# pi_zero_shield_v1_KW.net
KiCad netlist of a schematic drawn in EAGLE
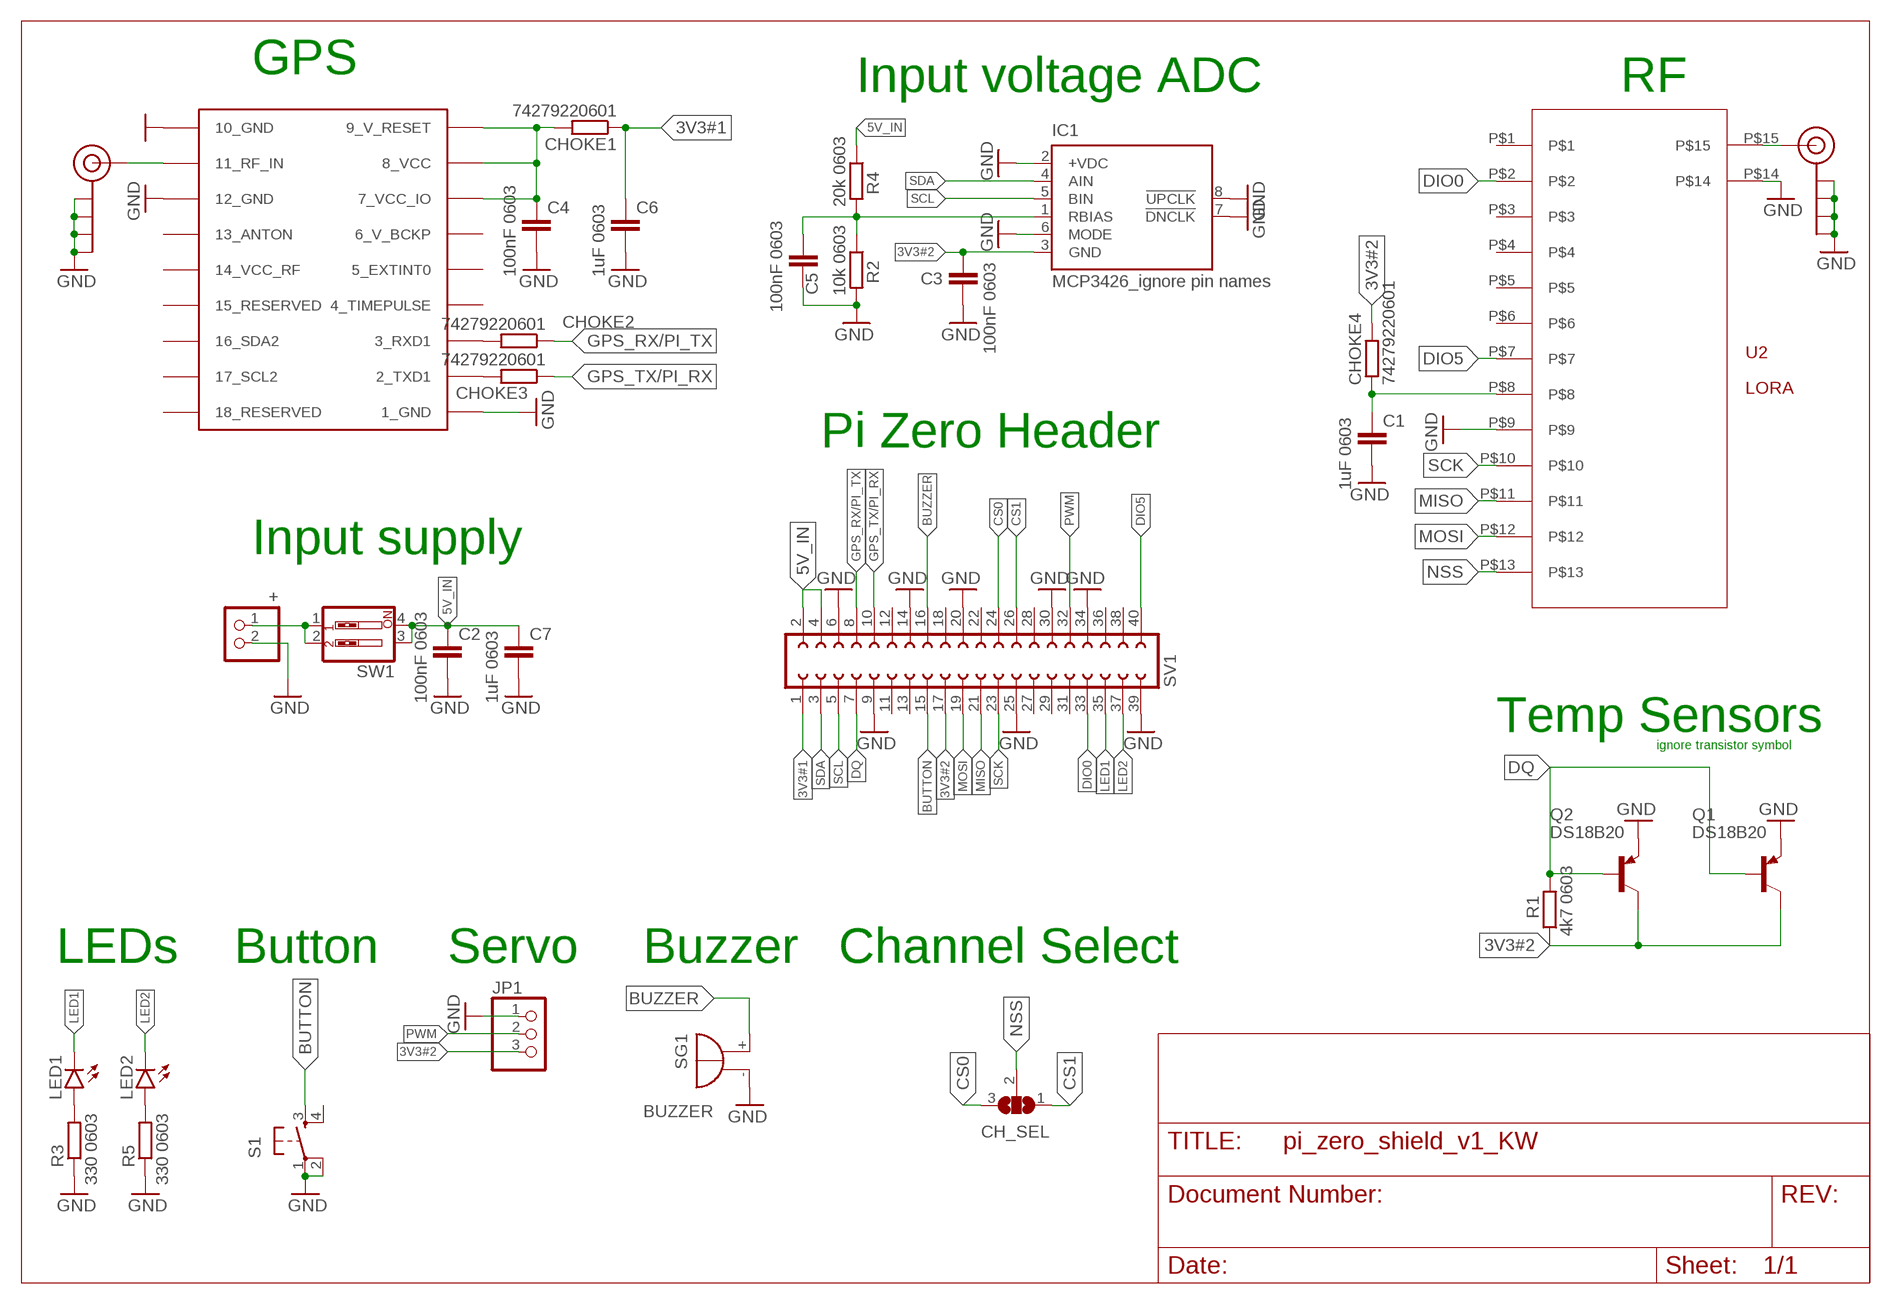
[diagram p0: schematic, sheet 1]

(export (version "E")
  (design (tool "Eeschema 10.0.6"))
  (components
    (comp (ref "+")
      (value "PINHD-1X2")
      (footprint "eagle-import:1X02")
      (libsource (lib "eagle-import") (part "PINHD-1X2"))
    )
    (comp (ref "C1")
      (value "1uF 0603")
      (footprint "eagle-import:C0603K")
      (libsource (lib "eagle-import") (part "C-EUC0603K"))
    )
    (comp (ref "C2")
      (value "100nF 0603")
      (footprint "eagle-import:C0603K")
      (libsource (lib "eagle-import") (part "C-EUC0603K"))
    )
    (comp (ref "C3")
      (value "100nF 0603")
      (footprint "eagle-import:C0603K")
      (libsource (lib "eagle-import") (part "C-EUC0603K"))
    )
    (comp (ref "C4")
      (value "100nF 0603")
      (footprint "eagle-import:C0603K")
      (libsource (lib "eagle-import") (part "C-EUC0603K"))
    )
    (comp (ref "C5")
      (value "100nF 0603")
      (footprint "eagle-import:C0603K")
      (libsource (lib "eagle-import") (part "C-EUC0603K"))
    )
    (comp (ref "C6")
      (value "1uF 0603")
      (footprint "eagle-import:C0603K")
      (libsource (lib "eagle-import") (part "C-EUC0603K"))
    )
    (comp (ref "C7")
      (value "1uF 0603")
      (footprint "eagle-import:C0603K")
      (libsource (lib "eagle-import") (part "C-EUC0603K"))
    )
    (comp (ref "CHOKE1")
      (value "74279220601")
      (footprint "eagle-import:M0805")
      (libsource (lib "eagle-import") (part "R-EU_M0805"))
    )
    (comp (ref "CHOKE2")
      (value "74279220601")
      (footprint "eagle-import:M0805")
      (libsource (lib "eagle-import") (part "R-EU_M0805"))
    )
    (comp (ref "CHOKE3")
      (value "74279220601")
      (footprint "eagle-import:M0805")
      (libsource (lib "eagle-import") (part "R-EU_M0805"))
    )
    (comp (ref "CHOKE4")
      (value "74279220601")
      (footprint "eagle-import:M0805")
      (libsource (lib "eagle-import") (part "R-EU_M0805"))
    )
    (comp (ref "CH_SEL")
      (value "SJ2W")
      (footprint "eagle-import:SJ_2")
      (libsource (lib "eagle-import") (part "SJ2W"))
    )
    (comp (ref "IC1")
      (value "MCP3426_ignore pin names")
      (footprint "eagle-import:SOIC08")
      (libsource (lib "eagle-import") (part "LS7183-SOIC"))
    )
    (comp (ref "J$1")
      (value "SMA_EDGE")
      (footprint "eagle-import:SMA-EDGE")
      (libsource (lib "eagle-import") (part "SMA_EDGE"))
    )
    (comp (ref "J$2")
      (value "SMA_EDGE")
      (footprint "eagle-import:SMA-EDGE")
      (libsource (lib "eagle-import") (part "SMA_EDGE"))
    )
    (comp (ref "JP1")
      (value "PINHD-1X3")
      (footprint "eagle-import:1X03")
      (libsource (lib "eagle-import") (part "PINHD-1X3"))
    )
    (comp (ref "LED1")
      (value "LEDSML0603")
      (footprint "eagle-import:SML0603")
      (libsource (lib "eagle-import") (part "LEDSML0603"))
    )
    (comp (ref "LED2")
      (value "LEDSML0603")
      (footprint "eagle-import:SML0603")
      (libsource (lib "eagle-import") (part "LEDSML0603"))
    )
    (comp (ref "Q1")
      (value "DS18B20")
      (footprint "eagle-import:TO92-CBE")
      (libsource (lib "eagle-import") (part "-?TO92MPSA56"))
    )
    (comp (ref "Q2")
      (value "DS18B20")
      (footprint "eagle-import:TO92-CBE")
      (libsource (lib "eagle-import") (part "-?TO92MPSA56"))
    )
    (comp (ref "R1")
      (value "4k7 0603")
      (footprint "eagle-import:R0603")
      (libsource (lib "eagle-import") (part "R-EU_R0603"))
    )
    (comp (ref "R2")
      (value "10k 0603")
      (footprint "eagle-import:R0603")
      (libsource (lib "eagle-import") (part "R-EU_R0603"))
    )
    (comp (ref "R3")
      (value "330 0603")
      (footprint "eagle-import:R0603")
      (libsource (lib "eagle-import") (part "R-EU_R0603"))
    )
    (comp (ref "R4")
      (value "20k 0603")
      (footprint "eagle-import:R0603")
      (libsource (lib "eagle-import") (part "R-EU_R0603"))
    )
    (comp (ref "R5")
      (value "330 0603")
      (footprint "eagle-import:R0603")
      (libsource (lib "eagle-import") (part "R-EU_R0603"))
    )
    (comp (ref "S1")
      (value "DTS-6")
      (footprint "eagle-import:DTS-6")
      (libsource (lib "eagle-import") (part "DTS-6"))
    )
    (comp (ref "SG1")
      (value "BUZZER")
      (footprint "eagle-import:BMT1205XH7.5")
      (libsource (lib "eagle-import") (part "BMT1205XH7.5"))
    )
    (comp (ref "SV1")
      (value "FE20-2")
      (footprint "eagle-import:FE20-2")
      (libsource (lib "eagle-import") (part "FE20-2"))
    )
    (comp (ref "SW1")
      (value "SW_DIP-2")
      (footprint "eagle-import:EDG-02")
      (libsource (lib "eagle-import") (part "SW_DIP-2"))
    )
    (comp (ref "U1")
      (value "U1")
      (footprint "eagle-import:UBLOX_MAX-6")
      (libsource (lib "eagle-import") (part "UBLOX_MAX-6"))
    )
    (comp (ref "U2")
      (value "LORA")
      (footprint "eagle-import:LORA_DRF")
      (libsource (lib "eagle-import") (part "LORA"))
    )
  )
  (nets
    (net (code "1") (name "3V3#1") (class "Default")
      (node (ref "C6") (pin "1") (pinfunction "1_1") (pintype "passive"))
      (node (ref "CHOKE1") (pin "1") (pinfunction "1_1") (pintype "passive"))
      (node (ref "SV1") (pin "1") (pinfunction "1_1") (pintype "passive"))
    )
    (net (code "2") (name "3V3#2") (class "Default")
      (node (ref "C3") (pin "1") (pinfunction "1_1") (pintype "passive"))
      (node (ref "CHOKE4") (pin "2") (pinfunction "2_2") (pintype "passive"))
      (node (ref "IC1") (pin "3") (pinfunction "GND_3") (pintype "power_in"))
      (node (ref "JP1") (pin "3") (pinfunction "3_3") (pintype "passive"))
      (node (ref "Q1") (pin "C") (pinfunction "C_C") (pintype "passive"))
      (node (ref "Q2") (pin "C") (pinfunction "C_C") (pintype "passive"))
      (node (ref "R1") (pin "1") (pinfunction "1_1") (pintype "passive"))
      (node (ref "SV1") (pin "17") (pinfunction "17_17") (pintype "passive"))
    )
    (net (code "3") (name "5V_IN") (class "Default")
      (node (ref "C2") (pin "1") (pinfunction "1_1") (pintype "passive"))
      (node (ref "C7") (pin "1") (pinfunction "1_1") (pintype "passive"))
      (node (ref "R4") (pin "1") (pinfunction "1_1") (pintype "passive"))
      (node (ref "SV1") (pin "2") (pinfunction "2_2") (pintype "passive"))
      (node (ref "SV1") (pin "4") (pinfunction "4_4") (pintype "passive"))
      (node (ref "SW1") (pin "3") (pinfunction "3_3") (pintype "passive"))
      (node (ref "SW1") (pin "4") (pinfunction "4_4") (pintype "passive"))
    )
    (net (code "4") (name "BUTTON") (class "Default")
      (node (ref "S1") (pin "3") (pinfunction "3_3") (pintype "passive"))
      (node (ref "SV1") (pin "15") (pinfunction "15_15") (pintype "passive"))
    )
    (net (code "5") (name "BUZZER") (class "Default")
      (node (ref "SG1") (pin "+") (pinfunction "+_+") (pintype "passive"))
      (node (ref "SV1") (pin "16") (pinfunction "16_16") (pintype "passive"))
    )
    (net (code "6") (name "CS0") (class "Default")
      (node (ref "CH_SEL") (pin "3") (pinfunction "3_3") (pintype "passive"))
      (node (ref "SV1") (pin "24") (pinfunction "24_24") (pintype "passive"))
    )
    (net (code "7") (name "CS1") (class "Default")
      (node (ref "CH_SEL") (pin "1") (pinfunction "1_1") (pintype "passive"))
      (node (ref "SV1") (pin "26") (pinfunction "26_26") (pintype "passive"))
    )
    (net (code "8") (name "DIO0") (class "Default")
      (node (ref "SV1") (pin "33") (pinfunction "33_33") (pintype "passive"))
      (node (ref "U2") (pin "P$2") (pinfunction "P$2_P$2") (pintype "bidirectional"))
    )
    (net (code "9") (name "DIO5") (class "Default")
      (node (ref "SV1") (pin "40") (pinfunction "40_40") (pintype "passive"))
      (node (ref "U2") (pin "P$7") (pinfunction "P$7_P$7") (pintype "bidirectional"))
    )
    (net (code "10") (name "DQ") (class "Default")
      (node (ref "Q1") (pin "B") (pinfunction "B_B") (pintype "passive"))
      (node (ref "Q2") (pin "B") (pinfunction "B_B") (pintype "passive"))
      (node (ref "R1") (pin "2") (pinfunction "2_2") (pintype "passive"))
      (node (ref "SV1") (pin "7") (pinfunction "7_7") (pintype "passive"))
    )
    (net (code "11") (name "GND") (class "Default")
      (node (ref "+") (pin "2") (pinfunction "2_2") (pintype "passive"))
      (node (ref "C1") (pin "2") (pinfunction "2_2") (pintype "passive"))
      (node (ref "C2") (pin "2") (pinfunction "2_2") (pintype "passive"))
      (node (ref "C3") (pin "2") (pinfunction "2_2") (pintype "passive"))
      (node (ref "C4") (pin "2") (pinfunction "2_2") (pintype "passive"))
      (node (ref "C5") (pin "2") (pinfunction "2_2") (pintype "passive"))
      (node (ref "C6") (pin "2") (pinfunction "2_2") (pintype "passive"))
      (node (ref "C7") (pin "2") (pinfunction "2_2") (pintype "passive"))
      (node (ref "IC1") (pin "2") (pinfunction "+VDC_2") (pintype "input"))
      (node (ref "IC1") (pin "6") (pinfunction "MODE_6") (pintype "input"))
      (node (ref "IC1") (pin "7") (pinfunction "~{DNCLK}_7") (pintype "input"))
      (node (ref "IC1") (pin "8") (pinfunction "~{UPCLK}_8") (pintype "input"))
      (node (ref "J$1") (pin "GND@0") (pinfunction "GND_GND@0") (pintype "bidirectional"))
      (node (ref "J$1") (pin "GND@1") (pinfunction "GND_GND@1") (pintype "bidirectional"))
      (node (ref "J$1") (pin "GND@2") (pinfunction "GND_GND@2") (pintype "bidirectional"))
      (node (ref "J$1") (pin "GND@3") (pinfunction "GND_GND@3") (pintype "bidirectional"))
      (node (ref "J$2") (pin "GND@0") (pinfunction "GND_GND@0") (pintype "bidirectional"))
      (node (ref "J$2") (pin "GND@1") (pinfunction "GND_GND@1") (pintype "bidirectional"))
      (node (ref "J$2") (pin "GND@2") (pinfunction "GND_GND@2") (pintype "bidirectional"))
      (node (ref "J$2") (pin "GND@3") (pinfunction "GND_GND@3") (pintype "bidirectional"))
      (node (ref "JP1") (pin "1") (pinfunction "1_1") (pintype "passive"))
      (node (ref "Q1") (pin "E") (pinfunction "E_E") (pintype "passive"))
      (node (ref "Q2") (pin "E") (pinfunction "E_E") (pintype "passive"))
      (node (ref "R2") (pin "2") (pinfunction "2_2") (pintype "passive"))
      (node (ref "R3") (pin "1") (pinfunction "1_1") (pintype "passive"))
      (node (ref "R5") (pin "1") (pinfunction "1_1") (pintype "passive"))
      (node (ref "S1") (pin "1") (pinfunction "1_1") (pintype "passive"))
      (node (ref "S1") (pin "2") (pinfunction "2_2") (pintype "passive"))
      (node (ref "SG1") (pin "-") (pinfunction "-_-") (pintype "passive"))
      (node (ref "SV1") (pin "14") (pinfunction "14_14") (pintype "passive"))
      (node (ref "SV1") (pin "20") (pinfunction "20_20") (pintype "passive"))
      (node (ref "SV1") (pin "25") (pinfunction "25_25") (pintype "passive"))
      (node (ref "SV1") (pin "30") (pinfunction "30_30") (pintype "passive"))
      (node (ref "SV1") (pin "34") (pinfunction "34_34") (pintype "passive"))
      (node (ref "SV1") (pin "39") (pinfunction "39_39") (pintype "passive"))
      (node (ref "SV1") (pin "6") (pinfunction "6_6") (pintype "passive"))
      (node (ref "SV1") (pin "9") (pinfunction "9_9") (pintype "passive"))
      (node (ref "U1") (pin "10_GND") (pinfunction "10_GND_10_GND") (pintype "power_in"))
      (node (ref "U1") (pin "12_GND") (pinfunction "12_GND_12_GND") (pintype "power_in"))
      (node (ref "U1") (pin "1_GND") (pinfunction "1_GND_1_GND") (pintype "power_in"))
      (node (ref "U2") (pin "P$14") (pinfunction "P$14_P$14") (pintype "bidirectional"))
      (node (ref "U2") (pin "P$9") (pinfunction "P$9_P$9") (pintype "bidirectional"))
    )
    (net (code "12") (name "GPS_RX{slash}PI_TX") (class "Default")
      (node (ref "CHOKE2") (pin "1") (pinfunction "1_1") (pintype "passive"))
      (node (ref "SV1") (pin "8") (pinfunction "8_8") (pintype "passive"))
    )
    (net (code "13") (name "GPS_TX{slash}PI_RX") (class "Default")
      (node (ref "CHOKE3") (pin "1") (pinfunction "1_1") (pintype "passive"))
      (node (ref "SV1") (pin "10") (pinfunction "10_10") (pintype "passive"))
    )
    (net (code "14") (name "LED1") (class "Default")
      (node (ref "LED1") (pin "C") (pinfunction "C_C") (pintype "passive"))
      (node (ref "SV1") (pin "35") (pinfunction "35_35") (pintype "passive"))
    )
    (net (code "15") (name "LED2") (class "Default")
      (node (ref "LED2") (pin "C") (pinfunction "C_C") (pintype "passive"))
      (node (ref "SV1") (pin "37") (pinfunction "37_37") (pintype "passive"))
    )
    (net (code "16") (name "MISO") (class "Default")
      (node (ref "SV1") (pin "21") (pinfunction "21_21") (pintype "passive"))
      (node (ref "U2") (pin "P$11") (pinfunction "P$11_P$11") (pintype "bidirectional"))
    )
    (net (code "17") (name "MOSI") (class "Default")
      (node (ref "SV1") (pin "19") (pinfunction "19_19") (pintype "passive"))
      (node (ref "U2") (pin "P$12") (pinfunction "P$12_P$12") (pintype "bidirectional"))
    )
    (net (code "18") (name "NSS") (class "Default")
      (node (ref "CH_SEL") (pin "2") (pinfunction "2_2") (pintype "passive"))
      (node (ref "U2") (pin "P$13") (pinfunction "P$13_P$13") (pintype "bidirectional"))
    )
    (net (code "19") (name "Net-(+-Pad1)") (class "Default")
      (node (ref "+") (pin "1") (pinfunction "1_1") (pintype "passive"))
      (node (ref "SW1") (pin "1") (pinfunction "1_1") (pintype "passive"))
      (node (ref "SW1") (pin "2") (pinfunction "2_2") (pintype "passive"))
    )
    (net (code "20") (name "Net-(C1-Pad1)") (class "Default")
      (node (ref "C1") (pin "1") (pinfunction "1_1") (pintype "passive"))
      (node (ref "CHOKE4") (pin "1") (pinfunction "1_1") (pintype "passive"))
      (node (ref "U2") (pin "P$8") (pinfunction "P$8_P$8") (pintype "bidirectional"))
    )
    (net (code "21") (name "Net-(C4-Pad1)") (class "Default")
      (node (ref "C4") (pin "1") (pinfunction "1_1") (pintype "passive"))
      (node (ref "CHOKE1") (pin "2") (pinfunction "2_2") (pintype "passive"))
      (node (ref "U1") (pin "7_VCC_IO") (pinfunction "7_VCC_IO_7_VCC_IO") (pintype "power_in"))
      (node (ref "U1") (pin "8_VCC") (pinfunction "8_VCC_8_VCC") (pintype "power_in"))
      (node (ref "U1") (pin "9_V_RESET") (pinfunction "9_V_RESET_9_V_RESET") (pintype "power_in"))
    )
    (net (code "22") (name "Net-(CHOKE2-Pad2)") (class "Default")
      (node (ref "CHOKE2") (pin "2") (pinfunction "2_2") (pintype "passive"))
      (node (ref "U1") (pin "3_RXD1") (pinfunction "3_RXD1_3_RXD1") (pintype "bidirectional"))
    )
    (net (code "23") (name "Net-(CHOKE3-Pad2)") (class "Default")
      (node (ref "CHOKE3") (pin "2") (pinfunction "2_2") (pintype "passive"))
      (node (ref "U1") (pin "2_TXD1") (pinfunction "2_TXD1_2_TXD1") (pintype "bidirectional"))
    )
    (net (code "24") (name "Net-(IC1-RBIAS)") (class "Default")
      (node (ref "C5") (pin "1") (pinfunction "1_1") (pintype "passive"))
      (node (ref "IC1") (pin "1") (pinfunction "RBIAS_1") (pintype "input"))
      (node (ref "R2") (pin "1") (pinfunction "1_1") (pintype "passive"))
      (node (ref "R4") (pin "2") (pinfunction "2_2") (pintype "passive"))
    )
    (net (code "25") (name "Net-(J$1-SIGNAL)") (class "Default")
      (node (ref "J$1") (pin "SIG") (pinfunction "SIGNAL_SIG") (pintype "bidirectional"))
      (node (ref "U1") (pin "11_RF_IN") (pinfunction "11_RF_IN_11_RF_IN") (pintype "bidirectional"))
    )
    (net (code "26") (name "Net-(J$2-SIGNAL)") (class "Default")
      (node (ref "J$2") (pin "SIG") (pinfunction "SIGNAL_SIG") (pintype "bidirectional"))
      (node (ref "U2") (pin "P$15") (pinfunction "P$15_P$15") (pintype "bidirectional"))
    )
    (net (code "27") (name "Net-(LED1-PadA)") (class "Default")
      (node (ref "LED1") (pin "A") (pinfunction "A_A") (pintype "passive"))
      (node (ref "R3") (pin "2") (pinfunction "2_2") (pintype "passive"))
    )
    (net (code "28") (name "Net-(LED2-PadA)") (class "Default")
      (node (ref "LED2") (pin "A") (pinfunction "A_A") (pintype "passive"))
      (node (ref "R5") (pin "2") (pinfunction "2_2") (pintype "passive"))
    )
    (net (code "29") (name "PWM") (class "Default")
      (node (ref "JP1") (pin "2") (pinfunction "2_2") (pintype "passive"))
      (node (ref "SV1") (pin "32") (pinfunction "32_32") (pintype "passive"))
    )
    (net (code "30") (name "SCK") (class "Default")
      (node (ref "SV1") (pin "23") (pinfunction "23_23") (pintype "passive"))
      (node (ref "U2") (pin "P$10") (pinfunction "P$10_P$10") (pintype "bidirectional"))
    )
    (net (code "31") (name "SCL") (class "Default")
      (node (ref "IC1") (pin "5") (pinfunction "BIN_5") (pintype "input"))
      (node (ref "SV1") (pin "5") (pinfunction "5_5") (pintype "passive"))
    )
    (net (code "32") (name "SDA") (class "Default")
      (node (ref "IC1") (pin "4") (pinfunction "AIN_4") (pintype "input"))
      (node (ref "SV1") (pin "3") (pinfunction "3_3") (pintype "passive"))
    )
    (net (code "33") (name "unconnected-(S1-Pad4)") (class "Default")
      (node (ref "S1") (pin "4") (pinfunction "4_4") (pintype "passive"))
    )
    (net (code "34") (name "unconnected-(SV1-Pad11)") (class "Default")
      (node (ref "SV1") (pin "11") (pinfunction "11_11") (pintype "passive"))
    )
    (net (code "35") (name "unconnected-(SV1-Pad12)") (class "Default")
      (node (ref "SV1") (pin "12") (pinfunction "12_12") (pintype "passive"))
    )
    (net (code "36") (name "unconnected-(SV1-Pad13)") (class "Default")
      (node (ref "SV1") (pin "13") (pinfunction "13_13") (pintype "passive"))
    )
    (net (code "37") (name "unconnected-(SV1-Pad18)") (class "Default")
      (node (ref "SV1") (pin "18") (pinfunction "18_18") (pintype "passive"))
    )
    (net (code "38") (name "unconnected-(SV1-Pad22)") (class "Default")
      (node (ref "SV1") (pin "22") (pinfunction "22_22") (pintype "passive"))
    )
    (net (code "39") (name "unconnected-(SV1-Pad27)") (class "Default")
      (node (ref "SV1") (pin "27") (pinfunction "27_27") (pintype "passive"))
    )
    (net (code "40") (name "unconnected-(SV1-Pad28)") (class "Default")
      (node (ref "SV1") (pin "28") (pinfunction "28_28") (pintype "passive"))
    )
    (net (code "41") (name "unconnected-(SV1-Pad29)") (class "Default")
      (node (ref "SV1") (pin "29") (pinfunction "29_29") (pintype "passive"))
    )
    (net (code "42") (name "unconnected-(SV1-Pad31)") (class "Default")
      (node (ref "SV1") (pin "31") (pinfunction "31_31") (pintype "passive"))
    )
    (net (code "43") (name "unconnected-(SV1-Pad36)") (class "Default")
      (node (ref "SV1") (pin "36") (pinfunction "36_36") (pintype "passive"))
    )
    (net (code "44") (name "unconnected-(SV1-Pad38)") (class "Default")
      (node (ref "SV1") (pin "38") (pinfunction "38_38") (pintype "passive"))
    )
    (net (code "45") (name "unconnected-(U1-Pad4_TIMEPULSE)") (class "Default")
      (node (ref "U1") (pin "4_TIMEPULSE") (pinfunction "4_TIMEPULSE_4_TIMEPULSE") (pintype "bidirectional"))
    )
    (net (code "46") (name "unconnected-(U1-Pad5_EXTINT0)") (class "Default")
      (node (ref "U1") (pin "5_EXTINT0") (pinfunction "5_EXTINT0_5_EXTINT0") (pintype "bidirectional"))
    )
    (net (code "47") (name "unconnected-(U1-Pad6_V_BCKP)") (class "Default")
      (node (ref "U1") (pin "6_V_BCKP") (pinfunction "6_V_BCKP_6_V_BCKP") (pintype "bidirectional"))
    )
    (net (code "48") (name "unconnected-(U1-Pad13_ANTON)") (class "Default")
      (node (ref "U1") (pin "13_ANTON") (pinfunction "13_ANTON_13_ANTON") (pintype "bidirectional"))
    )
    (net (code "49") (name "unconnected-(U1-Pad14_VCC_RF)") (class "Default")
      (node (ref "U1") (pin "14_VCC_RF") (pinfunction "14_VCC_RF_14_VCC_RF") (pintype "bidirectional"))
    )
    (net (code "50") (name "unconnected-(U1-Pad15_RESERVED)") (class "Default")
      (node (ref "U1") (pin "15_RESERVED") (pinfunction "15_RESERVED_15_RESERVED") (pintype "bidirectional"))
    )
    (net (code "51") (name "unconnected-(U1-Pad16_SDA2)") (class "Default")
      (node (ref "U1") (pin "16_SDA2") (pinfunction "16_SDA2_16_SDA2") (pintype "bidirectional"))
    )
    (net (code "52") (name "unconnected-(U1-Pad17_SCL2)") (class "Default")
      (node (ref "U1") (pin "17_SCL2") (pinfunction "17_SCL2_17_SCL2") (pintype "bidirectional"))
    )
    (net (code "53") (name "unconnected-(U1-Pad18_RESERVED)") (class "Default")
      (node (ref "U1") (pin "18_RESERVED") (pinfunction "18_RESERVED_18_RESERVED") (pintype "bidirectional"))
    )
    (net (code "54") (name "unconnected-(U2-PadP$1)") (class "Default")
      (node (ref "U2") (pin "P$1") (pinfunction "P$1_P$1") (pintype "bidirectional"))
    )
    (net (code "55") (name "unconnected-(U2-PadP$3)") (class "Default")
      (node (ref "U2") (pin "P$3") (pinfunction "P$3_P$3") (pintype "bidirectional"))
    )
    (net (code "56") (name "unconnected-(U2-PadP$4)") (class "Default")
      (node (ref "U2") (pin "P$4") (pinfunction "P$4_P$4") (pintype "bidirectional"))
    )
    (net (code "57") (name "unconnected-(U2-PadP$5)") (class "Default")
      (node (ref "U2") (pin "P$5") (pinfunction "P$5_P$5") (pintype "bidirectional"))
    )
    (net (code "58") (name "unconnected-(U2-PadP$6)") (class "Default")
      (node (ref "U2") (pin "P$6") (pinfunction "P$6_P$6") (pintype "bidirectional"))
    )
  )
)
